# Sp_ndingsregulator_V1_0.net
KiCad netlist of a schematic drawn in EAGLE
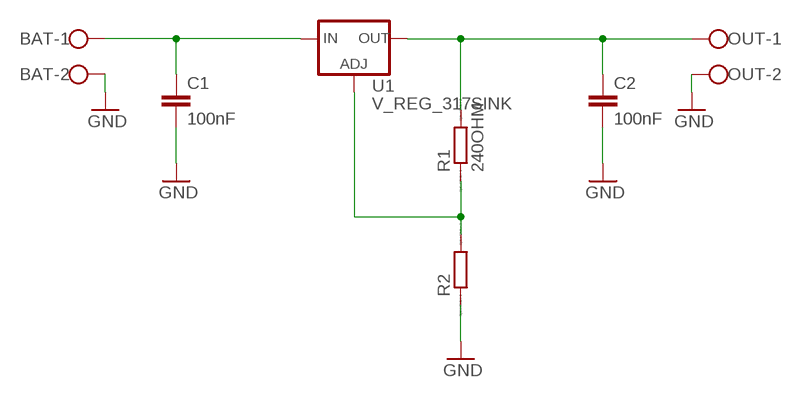
[diagram p0: schematic, sheet 1]

(export (version "E")
  (design (tool "Eeschema 10.0.6"))
  (components
    (comp (ref "BAT")
      (value "W237-102")
      (footprint "eagle-import:W237-102")
      (fields (field (name "MPN") "237-102"))
      (libsource (lib "eagle-import") (part "W237-102"))
    )
    (comp (ref "C1")
      (value "100nF")
      (footprint "eagle-import:C7.5B3")
      (libsource (lib "eagle-import") (part "C7.5/3"))
    )
    (comp (ref "C2")
      (value "100nF")
      (footprint "eagle-import:C7.5B3")
      (libsource (lib "eagle-import") (part "C7.5/3"))
    )
    (comp (ref "OUT")
      (value "W237-102")
      (footprint "eagle-import:W237-102")
      (fields (field (name "MPN") "237-102"))
      (libsource (lib "eagle-import") (part "W237-102"))
    )
    (comp (ref "R1")
      (value "240OHM")
      (footprint "eagle-import:0204_5")
      (libsource (lib "eagle-import") (part "R-EU_0204_5"))
    )
    (comp (ref "R2")
      (value "R-EU_0204_5")
      (footprint "eagle-import:0204_5")
      (libsource (lib "eagle-import") (part "R-EU_0204_5"))
    )
    (comp (ref "U1")
      (value "V_REG_317SINK")
      (footprint "eagle-import:TO220-ADJ")
      (libsource (lib "eagle-import") (part "V_REG_317SINK"))
    )
  )
  (nets
    (net (code "1") (name "GND") (class "Default")
      (node (ref "BAT") (pin "2") (pinfunction "KL_2") (pintype "passive"))
      (node (ref "C1") (pin "2") (pinfunction "2_2") (pintype "passive"))
      (node (ref "C2") (pin "2") (pinfunction "2_2") (pintype "passive"))
      (node (ref "OUT") (pin "2") (pinfunction "KL_2") (pintype "passive"))
      (node (ref "R2") (pin "1") (pinfunction "1_1") (pintype "passive"))
    )
    (net (code "2") (name "Net-(BATA-KL)") (class "Default")
      (node (ref "BAT") (pin "1") (pinfunction "KL_1") (pintype "passive"))
      (node (ref "C1") (pin "1") (pinfunction "1_1") (pintype "passive"))
      (node (ref "U1") (pin "IN") (pinfunction "IN_IN") (pintype "input"))
    )
    (net (code "3") (name "Net-(OUTA-KL)") (class "Default")
      (node (ref "C2") (pin "1") (pinfunction "1_1") (pintype "passive"))
      (node (ref "OUT") (pin "1") (pinfunction "KL_1") (pintype "passive"))
      (node (ref "R1") (pin "2") (pinfunction "2_2") (pintype "passive"))
      (node (ref "U1") (pin "OUT") (pinfunction "OUT_OUT") (pintype "output"))
    )
    (net (code "4") (name "Net-(R1-Pad1)") (class "Default")
      (node (ref "R1") (pin "1") (pinfunction "1_1") (pintype "passive"))
      (node (ref "R2") (pin "2") (pinfunction "2_2") (pintype "passive"))
      (node (ref "U1") (pin "ADJ") (pinfunction "ADJ_ADJ") (pintype "input"))
    )
  )
)
